# terminator-sil.net
KiCad netlist of a schematic drawn in EAGLE
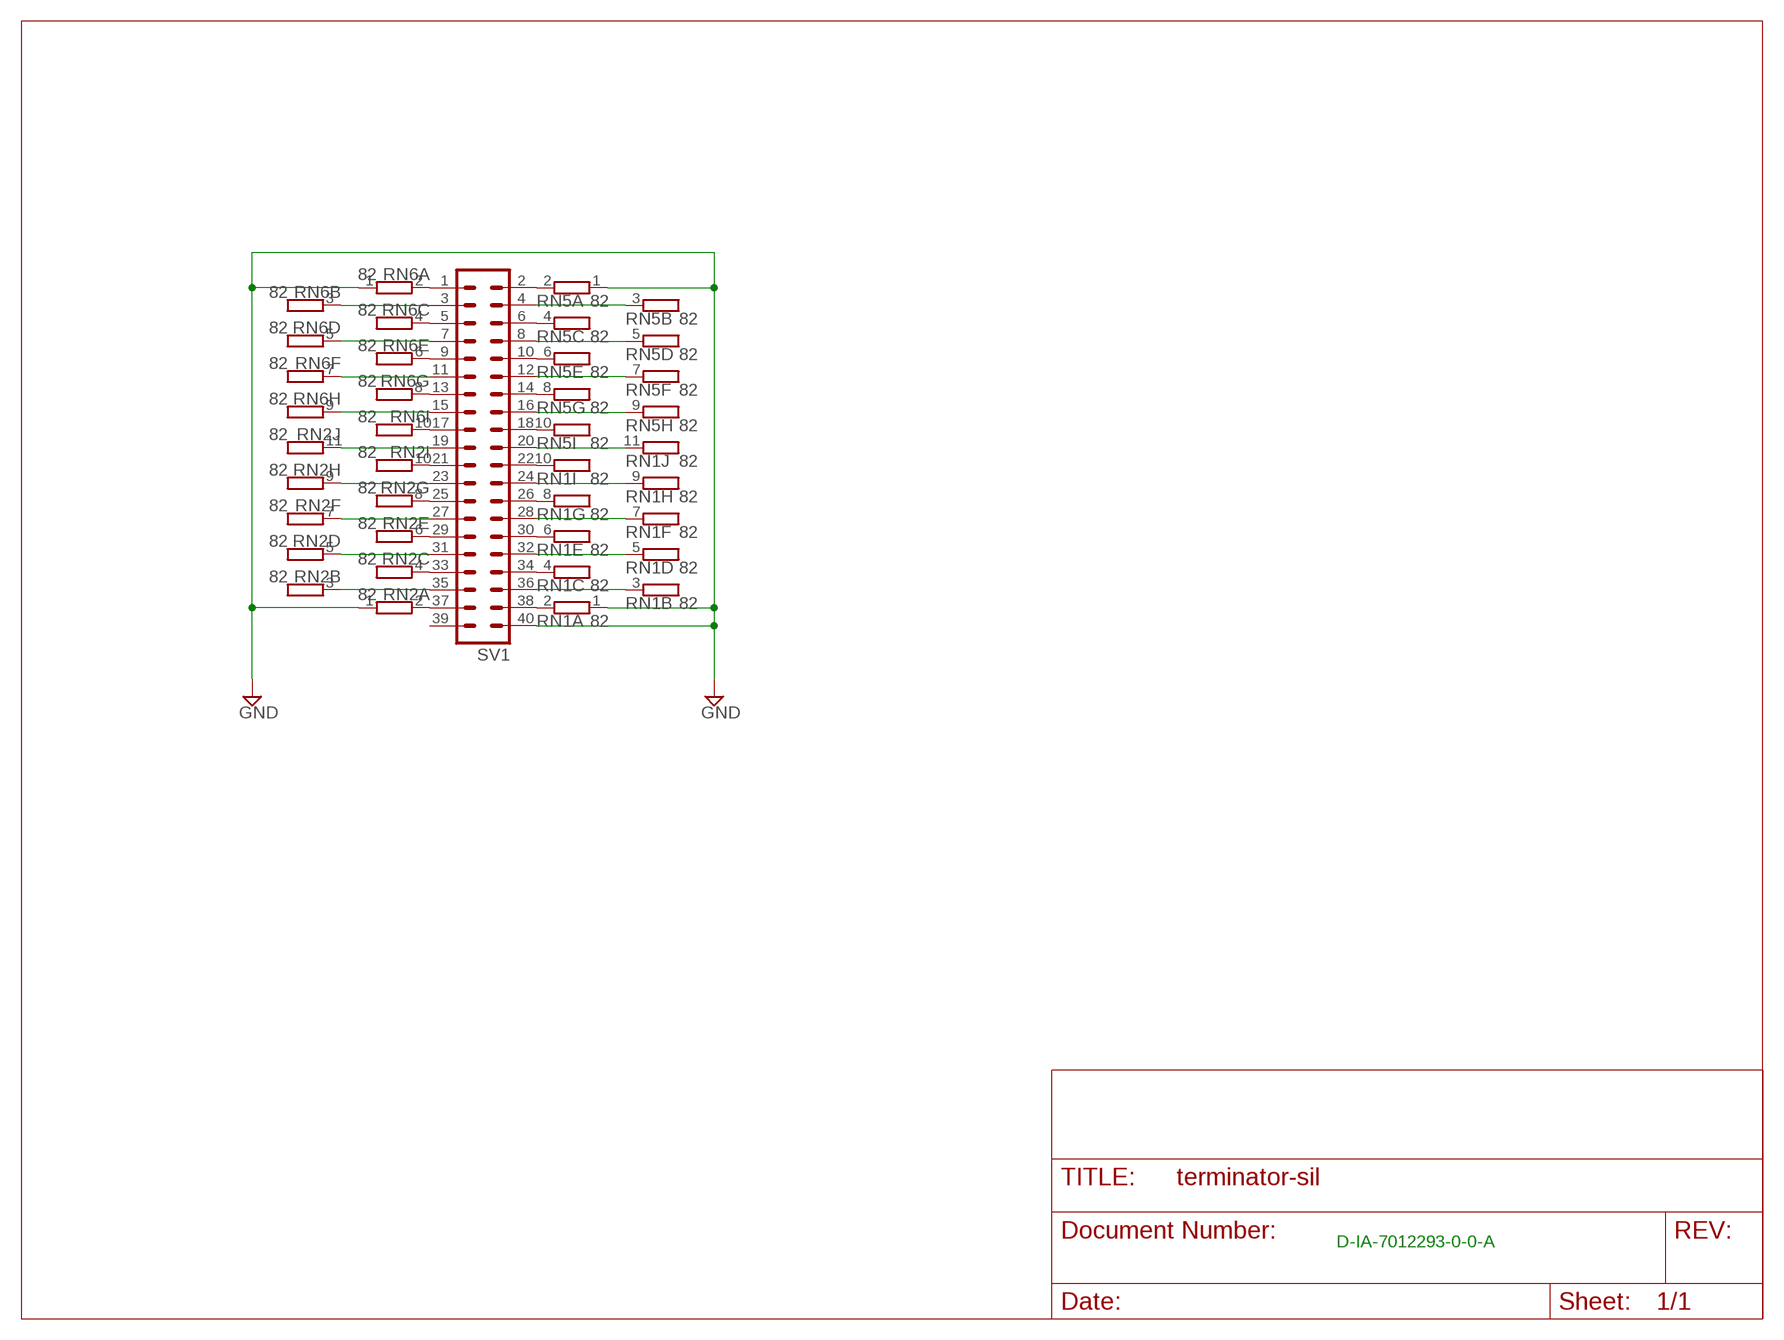
[diagram p0: schematic, sheet 1]

(export (version "E")
  (design (tool "Eeschema 10.0.6"))
  (components
    (comp (ref "RN1")
      (value "82")
      (footprint "eagle-import:SIL11")
      (libsource (lib "eagle-import") (part "GE10R"))
    )
    (comp (ref "RN2")
      (value "82")
      (footprint "eagle-import:SIL11")
      (libsource (lib "eagle-import") (part "GE10R"))
    )
    (comp (ref "RN5")
      (value "82")
      (footprint "eagle-import:SIL10")
      (libsource (lib "eagle-import") (part "GE09R"))
    )
    (comp (ref "RN6")
      (value "82")
      (footprint "eagle-import:SIL10")
      (libsource (lib "eagle-import") (part "GE09R"))
    )
    (comp (ref "SV1")
      (value "MA20-2")
      (footprint "eagle-import:MA20-2")
      (libsource (lib "eagle-import") (part "MA20-2"))
    )
  )
  (nets
    (net (code "1") (name "GND") (class "Default")
      (node (ref "RN1") (pin "1") (pinfunction "1_1") (pintype "passive"))
      (node (ref "RN2") (pin "1") (pinfunction "1_1") (pintype "passive"))
      (node (ref "RN5") (pin "1") (pinfunction "1_1") (pintype "passive"))
      (node (ref "RN6") (pin "1") (pinfunction "1_1") (pintype "passive"))
      (node (ref "SV1") (pin "40") (pinfunction "40_40") (pintype "passive"))
    )
    (net (code "2") (name "Net-(RN1-Pad2)") (class "Default")
      (node (ref "RN1") (pin "2") (pinfunction "2_2") (pintype "passive"))
      (node (ref "SV1") (pin "38") (pinfunction "38_38") (pintype "passive"))
    )
    (net (code "3") (name "Net-(RN1B-2)") (class "Default")
      (node (ref "RN1") (pin "3") (pinfunction "2_3") (pintype "passive"))
      (node (ref "SV1") (pin "36") (pinfunction "36_36") (pintype "passive"))
    )
    (net (code "4") (name "Net-(RN1C-2)") (class "Default")
      (node (ref "RN1") (pin "4") (pinfunction "2_4") (pintype "passive"))
      (node (ref "SV1") (pin "34") (pinfunction "34_34") (pintype "passive"))
    )
    (net (code "5") (name "Net-(RN1D-2)") (class "Default")
      (node (ref "RN1") (pin "5") (pinfunction "2_5") (pintype "passive"))
      (node (ref "SV1") (pin "32") (pinfunction "32_32") (pintype "passive"))
    )
    (net (code "6") (name "Net-(RN1E-2)") (class "Default")
      (node (ref "RN1") (pin "6") (pinfunction "2_6") (pintype "passive"))
      (node (ref "SV1") (pin "30") (pinfunction "30_30") (pintype "passive"))
    )
    (net (code "7") (name "Net-(RN1F-2)") (class "Default")
      (node (ref "RN1") (pin "7") (pinfunction "2_7") (pintype "passive"))
      (node (ref "SV1") (pin "28") (pinfunction "28_28") (pintype "passive"))
    )
    (net (code "8") (name "Net-(RN1G-2)") (class "Default")
      (node (ref "RN1") (pin "8") (pinfunction "2_8") (pintype "passive"))
      (node (ref "SV1") (pin "26") (pinfunction "26_26") (pintype "passive"))
    )
    (net (code "9") (name "Net-(RN1H-2)") (class "Default")
      (node (ref "RN1") (pin "9") (pinfunction "2_9") (pintype "passive"))
      (node (ref "SV1") (pin "24") (pinfunction "24_24") (pintype "passive"))
    )
    (net (code "10") (name "Net-(RN1I-2)") (class "Default")
      (node (ref "RN1") (pin "10") (pinfunction "2_10") (pintype "passive"))
      (node (ref "SV1") (pin "22") (pinfunction "22_22") (pintype "passive"))
    )
    (net (code "11") (name "Net-(RN1J-2)") (class "Default")
      (node (ref "RN1") (pin "11") (pinfunction "2_11") (pintype "passive"))
      (node (ref "SV1") (pin "20") (pinfunction "20_20") (pintype "passive"))
    )
    (net (code "12") (name "Net-(RN2-Pad2)") (class "Default")
      (node (ref "RN2") (pin "2") (pinfunction "2_2") (pintype "passive"))
      (node (ref "SV1") (pin "37") (pinfunction "37_37") (pintype "passive"))
    )
    (net (code "13") (name "Net-(RN2B-2)") (class "Default")
      (node (ref "RN2") (pin "3") (pinfunction "2_3") (pintype "passive"))
      (node (ref "SV1") (pin "35") (pinfunction "35_35") (pintype "passive"))
    )
    (net (code "14") (name "Net-(RN2C-2)") (class "Default")
      (node (ref "RN2") (pin "4") (pinfunction "2_4") (pintype "passive"))
      (node (ref "SV1") (pin "33") (pinfunction "33_33") (pintype "passive"))
    )
    (net (code "15") (name "Net-(RN2D-2)") (class "Default")
      (node (ref "RN2") (pin "5") (pinfunction "2_5") (pintype "passive"))
      (node (ref "SV1") (pin "31") (pinfunction "31_31") (pintype "passive"))
    )
    (net (code "16") (name "Net-(RN2E-2)") (class "Default")
      (node (ref "RN2") (pin "6") (pinfunction "2_6") (pintype "passive"))
      (node (ref "SV1") (pin "29") (pinfunction "29_29") (pintype "passive"))
    )
    (net (code "17") (name "Net-(RN2F-2)") (class "Default")
      (node (ref "RN2") (pin "7") (pinfunction "2_7") (pintype "passive"))
      (node (ref "SV1") (pin "27") (pinfunction "27_27") (pintype "passive"))
    )
    (net (code "18") (name "Net-(RN2G-2)") (class "Default")
      (node (ref "RN2") (pin "8") (pinfunction "2_8") (pintype "passive"))
      (node (ref "SV1") (pin "25") (pinfunction "25_25") (pintype "passive"))
    )
    (net (code "19") (name "Net-(RN2H-2)") (class "Default")
      (node (ref "RN2") (pin "9") (pinfunction "2_9") (pintype "passive"))
      (node (ref "SV1") (pin "23") (pinfunction "23_23") (pintype "passive"))
    )
    (net (code "20") (name "Net-(RN2I-2)") (class "Default")
      (node (ref "RN2") (pin "10") (pinfunction "2_10") (pintype "passive"))
      (node (ref "SV1") (pin "21") (pinfunction "21_21") (pintype "passive"))
    )
    (net (code "21") (name "Net-(RN2J-2)") (class "Default")
      (node (ref "RN2") (pin "11") (pinfunction "2_11") (pintype "passive"))
      (node (ref "SV1") (pin "19") (pinfunction "19_19") (pintype "passive"))
    )
    (net (code "22") (name "Net-(RN5-Pad2)") (class "Default")
      (node (ref "RN5") (pin "2") (pinfunction "2_2") (pintype "passive"))
      (node (ref "SV1") (pin "2") (pinfunction "2_2") (pintype "passive"))
    )
    (net (code "23") (name "Net-(RN5B-2)") (class "Default")
      (node (ref "RN5") (pin "3") (pinfunction "2_3") (pintype "passive"))
      (node (ref "SV1") (pin "4") (pinfunction "4_4") (pintype "passive"))
    )
    (net (code "24") (name "Net-(RN5C-2)") (class "Default")
      (node (ref "RN5") (pin "4") (pinfunction "2_4") (pintype "passive"))
      (node (ref "SV1") (pin "6") (pinfunction "6_6") (pintype "passive"))
    )
    (net (code "25") (name "Net-(RN5D-2)") (class "Default")
      (node (ref "RN5") (pin "5") (pinfunction "2_5") (pintype "passive"))
      (node (ref "SV1") (pin "8") (pinfunction "8_8") (pintype "passive"))
    )
    (net (code "26") (name "Net-(RN5E-2)") (class "Default")
      (node (ref "RN5") (pin "6") (pinfunction "2_6") (pintype "passive"))
      (node (ref "SV1") (pin "10") (pinfunction "10_10") (pintype "passive"))
    )
    (net (code "27") (name "Net-(RN5F-2)") (class "Default")
      (node (ref "RN5") (pin "7") (pinfunction "2_7") (pintype "passive"))
      (node (ref "SV1") (pin "12") (pinfunction "12_12") (pintype "passive"))
    )
    (net (code "28") (name "Net-(RN5G-2)") (class "Default")
      (node (ref "RN5") (pin "8") (pinfunction "2_8") (pintype "passive"))
      (node (ref "SV1") (pin "14") (pinfunction "14_14") (pintype "passive"))
    )
    (net (code "29") (name "Net-(RN5H-2)") (class "Default")
      (node (ref "RN5") (pin "9") (pinfunction "2_9") (pintype "passive"))
      (node (ref "SV1") (pin "16") (pinfunction "16_16") (pintype "passive"))
    )
    (net (code "30") (name "Net-(RN5I-2)") (class "Default")
      (node (ref "RN5") (pin "10") (pinfunction "2_10") (pintype "passive"))
      (node (ref "SV1") (pin "18") (pinfunction "18_18") (pintype "passive"))
    )
    (net (code "31") (name "Net-(RN6-Pad2)") (class "Default")
      (node (ref "RN6") (pin "2") (pinfunction "2_2") (pintype "passive"))
      (node (ref "SV1") (pin "1") (pinfunction "1_1") (pintype "passive"))
    )
    (net (code "32") (name "Net-(RN6B-2)") (class "Default")
      (node (ref "RN6") (pin "3") (pinfunction "2_3") (pintype "passive"))
      (node (ref "SV1") (pin "3") (pinfunction "3_3") (pintype "passive"))
    )
    (net (code "33") (name "Net-(RN6C-2)") (class "Default")
      (node (ref "RN6") (pin "4") (pinfunction "2_4") (pintype "passive"))
      (node (ref "SV1") (pin "5") (pinfunction "5_5") (pintype "passive"))
    )
    (net (code "34") (name "Net-(RN6D-2)") (class "Default")
      (node (ref "RN6") (pin "5") (pinfunction "2_5") (pintype "passive"))
      (node (ref "SV1") (pin "7") (pinfunction "7_7") (pintype "passive"))
    )
    (net (code "35") (name "Net-(RN6E-2)") (class "Default")
      (node (ref "RN6") (pin "6") (pinfunction "2_6") (pintype "passive"))
      (node (ref "SV1") (pin "9") (pinfunction "9_9") (pintype "passive"))
    )
    (net (code "36") (name "Net-(RN6F-2)") (class "Default")
      (node (ref "RN6") (pin "7") (pinfunction "2_7") (pintype "passive"))
      (node (ref "SV1") (pin "11") (pinfunction "11_11") (pintype "passive"))
    )
    (net (code "37") (name "Net-(RN6G-2)") (class "Default")
      (node (ref "RN6") (pin "8") (pinfunction "2_8") (pintype "passive"))
      (node (ref "SV1") (pin "13") (pinfunction "13_13") (pintype "passive"))
    )
    (net (code "38") (name "Net-(RN6H-2)") (class "Default")
      (node (ref "RN6") (pin "9") (pinfunction "2_9") (pintype "passive"))
      (node (ref "SV1") (pin "15") (pinfunction "15_15") (pintype "passive"))
    )
    (net (code "39") (name "Net-(RN6I-2)") (class "Default")
      (node (ref "RN6") (pin "10") (pinfunction "2_10") (pintype "passive"))
      (node (ref "SV1") (pin "17") (pinfunction "17_17") (pintype "passive"))
    )
    (net (code "40") (name "unconnected-(SV1-Pad39)") (class "Default")
      (node (ref "SV1") (pin "39") (pinfunction "39_39") (pintype "passive"))
    )
  )
)
